# Toilet_Timer.net
KiCad netlist of a schematic drawn in Altium Designer
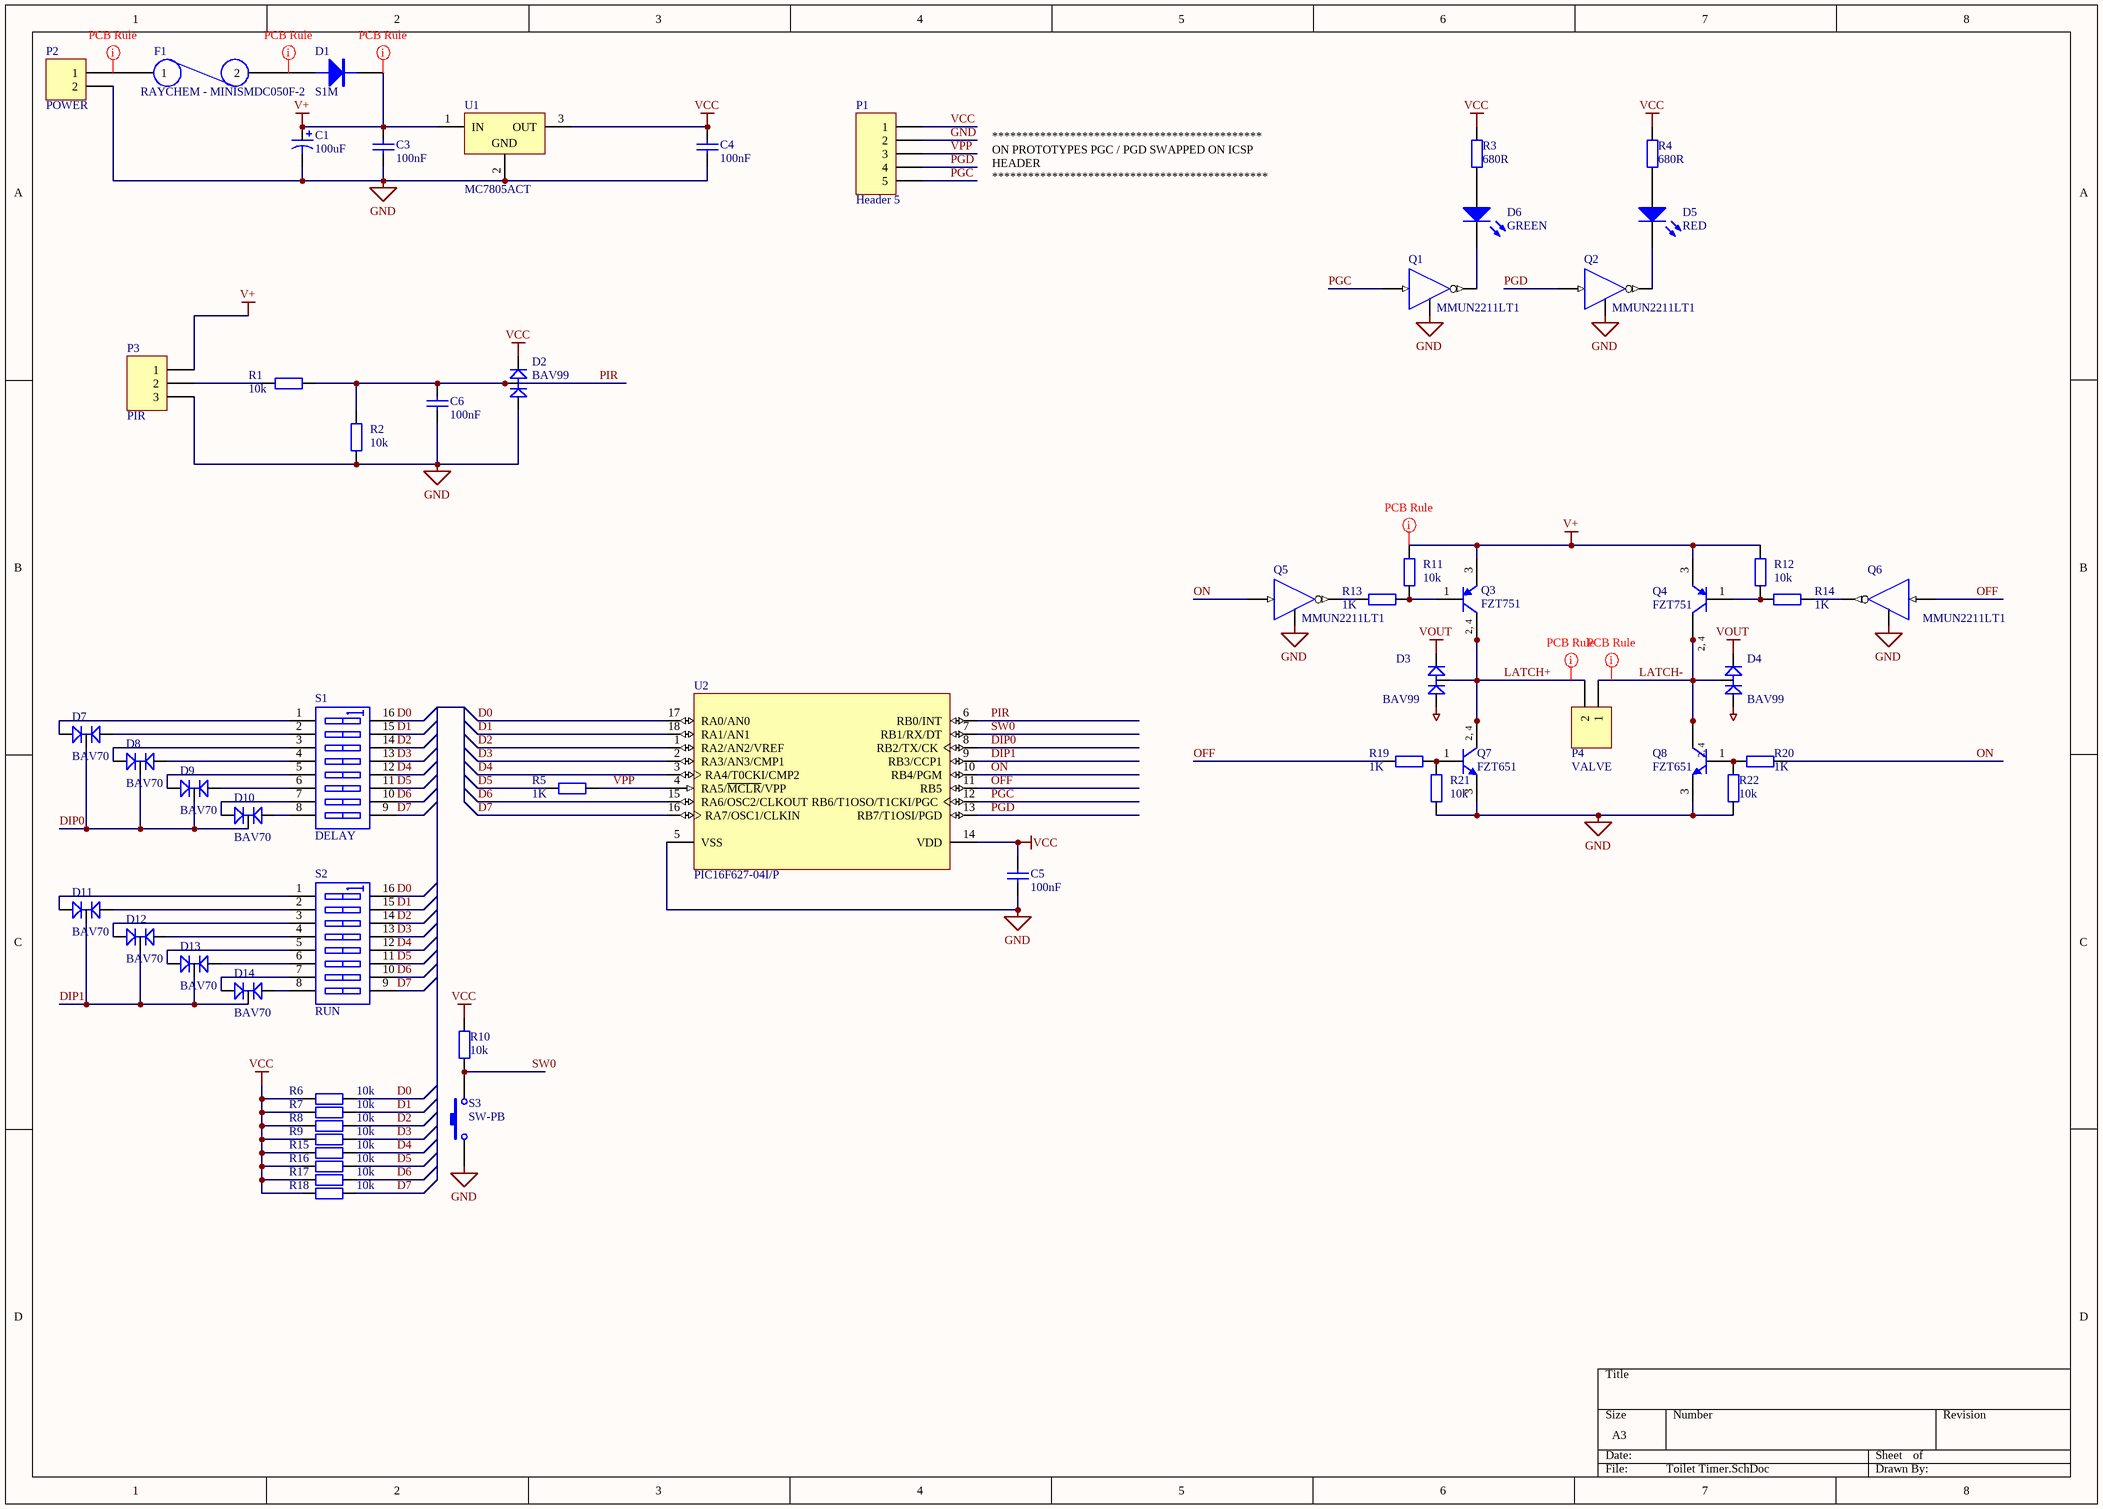
[diagram p0: Toilet Timer.SchDoc]

(export (version "E")
  (design (tool "Eeschema 10.0.6"))
  (components
    (comp (ref "C1")
      (value "100uF")
      (footprint "CAP, SMD E CASE")
      (description "Polarized Capacitor (Radial)")
      (fields (field (name "MOUSER PART NO.") "647-UVR1H101MPD1TA") (field (name "Comment") "Cap Pol1"))
      (libsource (lib "Miscellaneous Devices") (part "Cap Pol1"))
    )
    (comp (ref "C3")
      (value "100nF")
      (footprint "CAP(3D) - 0805")
      (description "Capacitor")
      (fields (field (name "MOUSER PART NO.") "K104Z15Y5VE5TH5") (field (name "Comment") "Cap"))
      (libsource (lib "Miscellaneous Devices") (part "Cap"))
    )
    (comp (ref "C4")
      (value "100nF")
      (footprint "CAP(3D) - 0805")
      (description "Capacitor")
      (fields (field (name "MOUSER PART NO.") "K104Z15Y5VE5TH5") (field (name "Comment") "Cap"))
      (libsource (lib "Miscellaneous Devices") (part "Cap"))
    )
    (comp (ref "C5")
      (value "100nF")
      (footprint "CAP(3D) - 0805")
      (description "Capacitor")
      (fields (field (name "MOUSER PART NO.") "K104Z15Y5VE5TH5") (field (name "Comment") "Cap"))
      (libsource (lib "Miscellaneous Devices") (part "Cap"))
    )
    (comp (ref "C6")
      (value "100nF")
      (footprint "CAP(3D) - 0805")
      (description "Capacitor")
      (fields (field (name "MOUSER PART NO.") "K104Z15Y5VE5TH5") (field (name "Comment") "Cap"))
      (libsource (lib "Miscellaneous Devices") (part "Cap"))
    )
    (comp (ref "D1")
      (value "S1M")
      (footprint "DO-214AC")
      (description "DIODE, POWER")
      (fields (field (name "MOUSER PART NO.") "821-S1M") (field (name "FARNELL PART NO.") "9843841"))
      (libsource (lib "401 CCPA") (part "DIODE"))
    )
    (comp (ref "D2")
      (value "BAV99")
      (footprint "SOT23-3L")
      (description "DUAL DIODE, BAV99")
      (fields (field (name "MOUSER PART NO.") "771-BAV99/T3") (field (name "FARNELL PART NO.") "9843612"))
      (libsource (lib "401 CCPA") (part "BAV99"))
    )
    (comp (ref "D3")
      (value "BAV99")
      (footprint "SOT23-3L")
      (description "DUAL DIODE, BAV99")
      (fields (field (name "MOUSER PART NO.") "771-BAV99/T3") (field (name "FARNELL PART NO.") "9843612"))
      (libsource (lib "401 CCPA") (part "BAV99"))
    )
    (comp (ref "D4")
      (value "BAV99")
      (footprint "SOT23-3L")
      (description "DUAL DIODE, BAV99")
      (fields (field (name "MOUSER PART NO.") "771-BAV99/T3") (field (name "FARNELL PART NO.") "9843612"))
      (libsource (lib "401 CCPA") (part "BAV99"))
    )
    (comp (ref "D5")
      (value "RED")
      (footprint "LED(3D) RED - 0805")
      (description "Typical INFRARED GaAs LED")
      (fields (field (name "MOUSER PART NO.") "606-4308H1"))
      (libsource (lib "Miscellaneous Devices") (part "LED0"))
    )
    (comp (ref "D6")
      (value "GREEN")
      (footprint "LED(3D) GREEN - 0805")
      (description "Typical INFRARED GaAs LED")
      (fields (field (name "MOUSER PART NO.") "606-4308H5"))
      (libsource (lib "Miscellaneous Devices") (part "LED0"))
    )
    (comp (ref "D7")
      (value "BAV70")
      (footprint "SOT23-3L")
      (description "DUAL DIODE, BAV99")
      (fields
        (field (name "FARNELL PART NO.") "9843612")
        (field (name "MANUFACTURER") "FAIRCHILD SEMICONDUCTOR")
      )
      (libsource (lib "Toilet Timer") (part "BAV70"))
    )
    (comp (ref "D8")
      (value "BAV70")
      (footprint "SOT23-3L")
      (description "DUAL DIODE, BAV99")
      (fields
        (field (name "FARNELL PART NO.") "9843612")
        (field (name "MANUFACTURER") "FAIRCHILD SEMICONDUCTOR")
      )
      (libsource (lib "Toilet Timer") (part "BAV70"))
    )
    (comp (ref "D9")
      (value "BAV70")
      (footprint "SOT23-3L")
      (description "DUAL DIODE, BAV99")
      (fields
        (field (name "FARNELL PART NO.") "9843612")
        (field (name "MANUFACTURER") "FAIRCHILD SEMICONDUCTOR")
      )
      (libsource (lib "Toilet Timer") (part "BAV70"))
    )
    (comp (ref "D10")
      (value "BAV70")
      (footprint "SOT23-3L")
      (description "DUAL DIODE, BAV99")
      (fields
        (field (name "FARNELL PART NO.") "9843612")
        (field (name "MANUFACTURER") "FAIRCHILD SEMICONDUCTOR")
      )
      (libsource (lib "Toilet Timer") (part "BAV70"))
    )
    (comp (ref "D11")
      (value "BAV70")
      (footprint "SOT23-3L")
      (description "DUAL DIODE, BAV99")
      (fields
        (field (name "FARNELL PART NO.") "9843612")
        (field (name "MANUFACTURER") "FAIRCHILD SEMICONDUCTOR")
      )
      (libsource (lib "Toilet Timer") (part "BAV70"))
    )
    (comp (ref "D12")
      (value "BAV70")
      (footprint "SOT23-3L")
      (description "DUAL DIODE, BAV99")
      (fields
        (field (name "FARNELL PART NO.") "9843612")
        (field (name "MANUFACTURER") "FAIRCHILD SEMICONDUCTOR")
      )
      (libsource (lib "Toilet Timer") (part "BAV70"))
    )
    (comp (ref "D13")
      (value "BAV70")
      (footprint "SOT23-3L")
      (description "DUAL DIODE, BAV99")
      (fields
        (field (name "FARNELL PART NO.") "9843612")
        (field (name "MANUFACTURER") "FAIRCHILD SEMICONDUCTOR")
      )
      (libsource (lib "Toilet Timer") (part "BAV70"))
    )
    (comp (ref "D14")
      (value "BAV70")
      (footprint "SOT23-3L")
      (description "DUAL DIODE, BAV99")
      (fields
        (field (name "FARNELL PART NO.") "9843612")
        (field (name "MANUFACTURER") "FAIRCHILD SEMICONDUCTOR")
      )
      (libsource (lib "Toilet Timer") (part "BAV70"))
    )
    (comp (ref "F1")
      (value "RAYCHEM - MINISMDC050F-2")
      (footprint "miniSMD Polyswitch")
      (fields
        (field (name "MOUSER PART NO.") "650-MINISMDC050F-2")
        (field (name "FARNELL PART NO.") "1175839")
        (field (name "MANUFACTURER") "Tyco Electronics / Raychem")
      )
      (libsource (lib "401 CCPA") (part "POLYSWITCH"))
    )
    (comp (ref "P1")
      (value "Header 5")
      (footprint "TERMINAL-6 POL")
      (description "Header, 5-Pin")
      (fields (field (name "MOUSER PART NO.") "571-6404565"))
      (libsource (lib "Miscellaneous Connectors") (part "Header 5"))
    )
    (comp (ref "P2")
      (value "POWER")
      (footprint "TYCO  1776112-2")
      (description "Header, 2-Pin")
      (fields (field (name "PUBLISHER") "Altium Limited"))
      (libsource (lib "Miscellaneous Connectors") (part "Header 2"))
    )
    (comp (ref "P3")
      (value "PIR")
      (footprint "TYCO  1776112-3")
      (description "Header, 3-Pin")
      (fields (field (name "PUBLISHER") "Altium Limited"))
      (libsource (lib "Miscellaneous Connectors") (part "Header 3"))
    )
    (comp (ref "P4")
      (value "VALVE")
      (footprint "TYCO  1776112-2")
      (description "Header, 2-Pin")
      (fields (field (name "PUBLISHER") "Altium Limited"))
      (libsource (lib "Miscellaneous Connectors") (part "Header 2"))
    )
    (comp (ref "Q1")
      (value "MMUN2211LT1")
      (footprint "SOT23-3L")
      (fields
        (field (name "MOUSER PART NO.") "863-MMUN2211LT1G")
        (field (name "FARNELL PART NO.") "9556648RL")
        (field (name "MANUFACTURER") "ON Semiconductor")
      )
      (libsource (lib "401 CCPA") (part "NPN DIGITAL TRANSISTOR"))
    )
    (comp (ref "Q2")
      (value "MMUN2211LT1")
      (footprint "SOT23-3L")
      (fields
        (field (name "MOUSER PART NO.") "863-MMUN2211LT1G")
        (field (name "FARNELL PART NO.") "9556648RL")
        (field (name "MANUFACTURER") "ON Semiconductor")
      )
      (libsource (lib "401 CCPA") (part "NPN DIGITAL TRANSISTOR"))
    )
    (comp (ref "Q3")
      (value "FZT751")
      (footprint "SOT223")
      (description "SOT223 PNP Silicon Planar High-Performance Transistor")
      (fields (field (name "PUBLISHER") "Altium Limited"))
      (libsource (lib "Zetex Discrete BJT") (part "FZT751"))
    )
    (comp (ref "Q4")
      (value "FZT751")
      (footprint "SOT223")
      (description "SOT223 PNP Silicon Planar High-Performance Transistor")
      (fields (field (name "PUBLISHER") "Altium Limited"))
      (libsource (lib "Zetex Discrete BJT") (part "FZT751"))
    )
    (comp (ref "Q5")
      (value "MMUN2211LT1")
      (footprint "SOT23-3L")
      (fields
        (field (name "MOUSER PART NO.") "863-MMUN2211LT1G")
        (field (name "FARNELL PART NO.") "9556648RL")
        (field (name "MANUFACTURER") "ON Semiconductor")
      )
      (libsource (lib "401 CCPA") (part "NPN DIGITAL TRANSISTOR"))
    )
    (comp (ref "Q6")
      (value "MMUN2211LT1")
      (footprint "SOT23-3L")
      (fields
        (field (name "MOUSER PART NO.") "863-MMUN2211LT1G")
        (field (name "FARNELL PART NO.") "9556648RL")
        (field (name "MANUFACTURER") "ON Semiconductor")
      )
      (libsource (lib "401 CCPA") (part "NPN DIGITAL TRANSISTOR"))
    )
    (comp (ref "Q7")
      (value "FZT651")
      (footprint "SOT223")
      (description "SOT223 NPN Silicon Planar High-Performance Transistor")
      (fields (field (name "PUBLISHER") "Altium Limited"))
      (libsource (lib "Zetex Discrete BJT") (part "FZT651"))
    )
    (comp (ref "Q8")
      (value "FZT651")
      (footprint "SOT223")
      (description "SOT223 NPN Silicon Planar High-Performance Transistor")
      (fields (field (name "PUBLISHER") "Altium Limited"))
      (libsource (lib "Zetex Discrete BJT") (part "FZT651"))
    )
    (comp (ref "R1")
      (value "10k")
      (footprint "RES(3D) - 0805")
      (description "Resistor")
      (fields (field (name "MOUSER PART NO.") "660-MF1/4LCT52R103J") (field (name "Comment") "Res2"))
      (libsource (lib "") (part "Res2_1"))
    )
    (comp (ref "R2")
      (value "10k")
      (footprint "RES(3D) - 0805")
      (description "Resistor")
      (fields (field (name "MOUSER PART NO.") "660-MF1/4LCT52R103J") (field (name "Comment") "Res2"))
      (libsource (lib "") (part "Res2_2"))
    )
    (comp (ref "R3")
      (value "680R")
      (footprint "RES(3D) - 0805")
      (description "Resistor")
      (fields (field (name "MOUSER PART NO.") "660-MF1/4DCT52R6800F") (field (name "Comment") "Res2"))
      (libsource (lib "") (part "Res2_2"))
    )
    (comp (ref "R4")
      (value "680R")
      (footprint "RES(3D) - 0805")
      (description "Resistor")
      (fields (field (name "MOUSER PART NO.") "660-MF1/4DCT52R6800F") (field (name "Comment") "Res2"))
      (libsource (lib "") (part "Res2_2"))
    )
    (comp (ref "R5")
      (value "1K")
      (footprint "RES(3D) - 0805")
      (description "Resistor")
      (fields (field (name "MOUSER PART NO.") "660-MF1/4DCT52R1102F") (field (name "Comment") "Res2"))
      (libsource (lib "") (part "Res2_1"))
    )
    (comp (ref "R6")
      (value "10k")
      (footprint "RES(3D) - 0805")
      (description "Resistor")
      (fields (field (name "MOUSER PART NO.") "660-MF1/4LCT52R103J") (field (name "Comment") "Res2"))
      (libsource (lib "Miscellaneous Devices") (part "Res2"))
    )
    (comp (ref "R7")
      (value "10k")
      (footprint "RES(3D) - 0805")
      (description "Resistor")
      (fields (field (name "MOUSER PART NO.") "660-MF1/4LCT52R103J") (field (name "Comment") "Res2"))
      (libsource (lib "Miscellaneous Devices") (part "Res2"))
    )
    (comp (ref "R8")
      (value "10k")
      (footprint "RES(3D) - 0805")
      (description "Resistor")
      (fields (field (name "MOUSER PART NO.") "660-MF1/4LCT52R103J") (field (name "Comment") "Res2"))
      (libsource (lib "Miscellaneous Devices") (part "Res2"))
    )
    (comp (ref "R9")
      (value "10k")
      (footprint "RES(3D) - 0805")
      (description "Resistor")
      (fields (field (name "MOUSER PART NO.") "660-MF1/4LCT52R103J") (field (name "Comment") "Res2"))
      (libsource (lib "Miscellaneous Devices") (part "Res2"))
    )
    (comp (ref "R10")
      (value "10k")
      (footprint "RES(3D) - 0805")
      (description "Resistor")
      (fields (field (name "MOUSER PART NO.") "660-MF1/4LCT52R103J") (field (name "Comment") "Res2"))
      (libsource (lib "") (part "Res2_3"))
    )
    (comp (ref "R11")
      (value "10k")
      (footprint "RES(3D) - 0805")
      (description "Resistor")
      (fields (field (name "MOUSER PART NO.") "660-MF1/4LCT52R103J") (field (name "Comment") "Res2"))
      (libsource (lib "") (part "Res2_2"))
    )
    (comp (ref "R12")
      (value "10k")
      (footprint "RES(3D) - 0805")
      (description "Resistor")
      (fields (field (name "MOUSER PART NO.") "660-MF1/4LCT52R103J") (field (name "Comment") "Res2"))
      (libsource (lib "") (part "Res2_2"))
    )
    (comp (ref "R13")
      (value "1K")
      (footprint "RES(3D) - 0805")
      (description "Resistor")
      (fields (field (name "MOUSER PART NO.") "660-MF1/4DCT52R1102F") (field (name "Comment") "Res2"))
      (libsource (lib "") (part "Res2_1"))
    )
    (comp (ref "R14")
      (value "1K")
      (footprint "RES(3D) - 0805")
      (description "Resistor")
      (fields (field (name "MOUSER PART NO.") "660-MF1/4DCT52R1102F") (field (name "Comment") "Res2"))
      (libsource (lib "") (part "Res2_3"))
    )
    (comp (ref "R15")
      (value "10k")
      (footprint "RES(3D) - 0805")
      (description "Resistor")
      (fields (field (name "MOUSER PART NO.") "660-MF1/4LCT52R103J") (field (name "Comment") "Res2"))
      (libsource (lib "Miscellaneous Devices") (part "Res2"))
    )
    (comp (ref "R16")
      (value "10k")
      (footprint "RES(3D) - 0805")
      (description "Resistor")
      (fields (field (name "MOUSER PART NO.") "660-MF1/4LCT52R103J") (field (name "Comment") "Res2"))
      (libsource (lib "Miscellaneous Devices") (part "Res2"))
    )
    (comp (ref "R17")
      (value "10k")
      (footprint "RES(3D) - 0805")
      (description "Resistor")
      (fields (field (name "MOUSER PART NO.") "660-MF1/4LCT52R103J") (field (name "Comment") "Res2"))
      (libsource (lib "Miscellaneous Devices") (part "Res2"))
    )
    (comp (ref "R18")
      (value "10k")
      (footprint "RES(3D) - 0805")
      (description "Resistor")
      (fields (field (name "MOUSER PART NO.") "660-MF1/4LCT52R103J") (field (name "Comment") "Res2"))
      (libsource (lib "Miscellaneous Devices") (part "Res2"))
    )
    (comp (ref "R19")
      (value "1K")
      (footprint "RES(3D) - 0805")
      (description "Resistor")
      (fields (field (name "MOUSER PART NO.") "660-MF1/4DCT52R1102F") (field (name "Comment") "Res2"))
      (libsource (lib "") (part "Res2_1"))
    )
    (comp (ref "R20")
      (value "1K")
      (footprint "RES(3D) - 0805")
      (description "Resistor")
      (fields (field (name "MOUSER PART NO.") "660-MF1/4DCT52R1102F") (field (name "Comment") "Res2"))
      (libsource (lib "") (part "Res2_3"))
    )
    (comp (ref "R21")
      (value "10k")
      (footprint "RES(3D) - 0805")
      (description "Resistor")
      (fields (field (name "MOUSER PART NO.") "660-MF1/4LCT52R103J") (field (name "Comment") "Res2"))
      (libsource (lib "") (part "Res2_2"))
    )
    (comp (ref "R22")
      (value "10k")
      (footprint "RES(3D) - 0805")
      (description "Resistor")
      (fields (field (name "MOUSER PART NO.") "660-MF1/4LCT52R103J") (field (name "Comment") "Res2"))
      (libsource (lib "") (part "Res2_1"))
    )
    (comp (ref "S1")
      (value "DELAY")
      (footprint "S-DIP-16")
      (description "DIP Switch, 8 Position, SPST")
      (fields (field (name "MOUSER PART NO.") "774-2068"))
      (libsource (lib "Miscellaneous Devices") (part "SW DIP-8"))
    )
    (comp (ref "S2")
      (value "RUN")
      (footprint "S-DIP-16")
      (description "DIP Switch, 8 Position, SPST")
      (fields (field (name "MOUSER PART NO.") "774-2068"))
      (libsource (lib "Miscellaneous Devices") (part "SW DIP-8"))
    )
    (comp (ref "S3")
      (value "SW-PB")
      (footprint "TACT 6MM")
      (description "Switch")
      (fields (field (name "MOUSER PART NO.") "642-MJTP1230"))
      (libsource (lib "Miscellaneous Devices") (part "SW-PB"))
    )
    (comp (ref "U1")
      (value "MC7805ACT")
      (footprint "7805 - DPAK")
      (description "3-Terminal Positive Fixed Voltage Regulator")
      (fields (field (name "MOUSER PART NO.") "512-LM7805ACT"))
      (libsource (lib "Motorola Power Mgt Voltage Regulator") (part "MC7805ACT"))
    )
    (comp (ref "U2")
      (value "PIC16F627-04I/P")
      (footprint "SOIC-18")
      (fields (field (name "MOUSER PART NO.") "579-PIC16F627A-I/P"))
      (libsource (lib "Microchip Microcontroller 8-Bit PIC16F") (part "PIC16F627-04I/P"))
    )
  )
  (nets
    (net (code "1") (name "/D0") (class "Default")
      (node (ref "R6") (pin "1") (pinfunction "1_1") (pintype "passive"))
      (node (ref "S1") (pin "16") (pinfunction "B1_16") (pintype "passive"))
      (node (ref "S2") (pin "16") (pinfunction "B1_16") (pintype "passive"))
      (node (ref "U2") (pin "17") (pinfunction "RA0/AN0_17") (pintype "bidirectional"))
    )
    (net (code "2") (name "/D1") (class "Default")
      (node (ref "R7") (pin "1") (pinfunction "1_1") (pintype "passive"))
      (node (ref "S1") (pin "15") (pinfunction "B2_15") (pintype "passive"))
      (node (ref "S2") (pin "15") (pinfunction "B2_15") (pintype "passive"))
      (node (ref "U2") (pin "18") (pinfunction "RA1/AN1_18") (pintype "bidirectional"))
    )
    (net (code "3") (name "/D2") (class "Default")
      (node (ref "R8") (pin "1") (pinfunction "1_1") (pintype "passive"))
      (node (ref "S1") (pin "14") (pinfunction "B3_14") (pintype "passive"))
      (node (ref "S2") (pin "14") (pinfunction "B3_14") (pintype "passive"))
      (node (ref "U2") (pin "1") (pinfunction "RA2/AN2/VREF_1") (pintype "bidirectional"))
    )
    (net (code "4") (name "/D3") (class "Default")
      (node (ref "R9") (pin "1") (pinfunction "1_1") (pintype "passive"))
      (node (ref "S1") (pin "13") (pinfunction "B4_13") (pintype "passive"))
      (node (ref "S2") (pin "13") (pinfunction "B4_13") (pintype "passive"))
      (node (ref "U2") (pin "2") (pinfunction "RA3/AN3/CMP1_2") (pintype "bidirectional"))
    )
    (net (code "5") (name "/D4") (class "Default")
      (node (ref "R15") (pin "1") (pinfunction "1_1") (pintype "passive"))
      (node (ref "S1") (pin "12") (pinfunction "B5_12") (pintype "passive"))
      (node (ref "S2") (pin "12") (pinfunction "B5_12") (pintype "passive"))
      (node (ref "U2") (pin "3") (pinfunction "RA4/T0CKI/CMP2_3") (pintype "bidirectional"))
    )
    (net (code "6") (name "/D5") (class "Default")
      (node (ref "R16") (pin "1") (pinfunction "1_1") (pintype "passive"))
      (node (ref "R5") (pin "1") (pinfunction "1_1") (pintype "passive"))
      (node (ref "S1") (pin "11") (pinfunction "B6_11") (pintype "passive"))
      (node (ref "S2") (pin "11") (pinfunction "B6_11") (pintype "passive"))
    )
    (net (code "7") (name "/D6") (class "Default")
      (node (ref "R17") (pin "1") (pinfunction "1_1") (pintype "passive"))
      (node (ref "S1") (pin "10") (pinfunction "B7_10") (pintype "passive"))
      (node (ref "S2") (pin "10") (pinfunction "B7_10") (pintype "passive"))
      (node (ref "U2") (pin "15") (pinfunction "RA6/OSC2/CLKOUT_15") (pintype "bidirectional"))
    )
    (net (code "8") (name "/D7") (class "Default")
      (node (ref "R18") (pin "1") (pinfunction "1_1") (pintype "passive"))
      (node (ref "S1") (pin "9") (pinfunction "B8_9") (pintype "passive"))
      (node (ref "S2") (pin "9") (pinfunction "B8_9") (pintype "passive"))
      (node (ref "U2") (pin "16") (pinfunction "RA7/OSC1/CLKIN_16") (pintype "bidirectional"))
    )
    (net (code "9") (name "/DIP0") (class "Default")
      (node (ref "D10") (pin "3") (pinfunction "C_3") (pintype "passive"))
      (node (ref "D7") (pin "3") (pinfunction "C_3") (pintype "passive"))
      (node (ref "D8") (pin "3") (pinfunction "C_3") (pintype "passive"))
      (node (ref "D9") (pin "3") (pinfunction "C_3") (pintype "passive"))
      (node (ref "U2") (pin "8") (pinfunction "RB2/TX/CK_8") (pintype "bidirectional"))
    )
    (net (code "10") (name "/DIP1") (class "Default")
      (node (ref "D11") (pin "3") (pinfunction "C_3") (pintype "passive"))
      (node (ref "D12") (pin "3") (pinfunction "C_3") (pintype "passive"))
      (node (ref "D13") (pin "3") (pinfunction "C_3") (pintype "passive"))
      (node (ref "D14") (pin "3") (pinfunction "C_3") (pintype "passive"))
      (node (ref "U2") (pin "9") (pinfunction "RB3/CCP1_9") (pintype "bidirectional"))
    )
    (net (code "11") (name "/LATCH+") (class "Default")
      (node (ref "D3") (pin "3") (pinfunction "C1/A2_3") (pintype "passive"))
      (node (ref "P4") (pin "2") (pinfunction "2_2") (pintype "passive"))
      (node (ref "Q3") (pin "2") (pinfunction "C_2") (pintype "passive"))
      (node (ref "Q3") (pin "4") (pinfunction "C_4") (pintype "passive"))
      (node (ref "Q7") (pin "2") (pinfunction "C_2") (pintype "passive"))
      (node (ref "Q7") (pin "4") (pinfunction "C_4") (pintype "passive"))
    )
    (net (code "12") (name "/LATCH-") (class "Default")
      (node (ref "D4") (pin "3") (pinfunction "C1/A2_3") (pintype "passive"))
      (node (ref "P4") (pin "1") (pinfunction "1_1") (pintype "passive"))
      (node (ref "Q4") (pin "2") (pinfunction "C_2") (pintype "passive"))
      (node (ref "Q4") (pin "4") (pinfunction "C_4") (pintype "passive"))
      (node (ref "Q8") (pin "2") (pinfunction "C_2") (pintype "passive"))
      (node (ref "Q8") (pin "4") (pinfunction "C_4") (pintype "passive"))
    )
    (net (code "13") (name "/OFF") (class "Default")
      (node (ref "Q6") (pin "1") (pinfunction "B_1") (pintype "input"))
      (node (ref "R19") (pin "1") (pinfunction "1_1") (pintype "passive"))
      (node (ref "U2") (pin "11") (pinfunction "RB5_11") (pintype "bidirectional"))
    )
    (net (code "14") (name "/ON") (class "Default")
      (node (ref "Q5") (pin "1") (pinfunction "B_1") (pintype "input"))
      (node (ref "R20") (pin "1") (pinfunction "1_1") (pintype "passive"))
      (node (ref "U2") (pin "10") (pinfunction "RB4/PGM_10") (pintype "bidirectional"))
    )
    (net (code "15") (name "/PGC") (class "Default")
      (node (ref "P1") (pin "5") (pinfunction "5_5") (pintype "passive"))
      (node (ref "Q1") (pin "1") (pinfunction "B_1") (pintype "input"))
      (node (ref "U2") (pin "12") (pinfunction "RB6/T1OSO/T1CKI/PGC_12") (pintype "bidirectional"))
    )
    (net (code "16") (name "/PGD") (class "Default")
      (node (ref "P1") (pin "4") (pinfunction "4_4") (pintype "passive"))
      (node (ref "Q2") (pin "1") (pinfunction "B_1") (pintype "input"))
      (node (ref "U2") (pin "13") (pinfunction "RB7/T1OSI/PGD_13") (pintype "bidirectional"))
    )
    (net (code "17") (name "/PIR") (class "Default")
      (node (ref "C6") (pin "2") (pinfunction "2_2") (pintype "passive"))
      (node (ref "D2") (pin "3") (pinfunction "C1/A2_3") (pintype "passive"))
      (node (ref "R1") (pin "2") (pinfunction "2_2") (pintype "passive"))
      (node (ref "R2") (pin "2") (pinfunction "2_2") (pintype "passive"))
      (node (ref "U2") (pin "6") (pinfunction "RB0/INT_6") (pintype "bidirectional"))
    )
    (net (code "18") (name "/SW0") (class "Default")
      (node (ref "R10") (pin "2") (pinfunction "2_2") (pintype "passive"))
      (node (ref "S3") (pin "2") (pinfunction "2_2") (pintype "passive"))
      (node (ref "U2") (pin "7") (pinfunction "RB1/RX/DT_7") (pintype "bidirectional"))
    )
    (net (code "19") (name "/VPP") (class "Default")
      (node (ref "P1") (pin "3") (pinfunction "3_3") (pintype "passive"))
      (node (ref "R5") (pin "2") (pinfunction "2_2") (pintype "passive"))
      (node (ref "U2") (pin "4") (pinfunction "RA5/~{MCLR}/VPP_4") (pintype "input"))
    )
    (net (code "20") (name "GND") (class "Default")
      (node (ref "C1") (pin "2") (pinfunction "2_2") (pintype "passive"))
      (node (ref "C3") (pin "1") (pinfunction "1_1") (pintype "passive"))
      (node (ref "C4") (pin "1") (pinfunction "1_1") (pintype "passive"))
      (node (ref "C5") (pin "1") (pinfunction "1_1") (pintype "passive"))
      (node (ref "C6") (pin "1") (pinfunction "1_1") (pintype "passive"))
      (node (ref "D2") (pin "1") (pinfunction "A1_1") (pintype "passive"))
      (node (ref "D3") (pin "1") (pinfunction "A1_1") (pintype "passive"))
      (node (ref "D4") (pin "1") (pinfunction "A1_1") (pintype "passive"))
      (node (ref "P1") (pin "2") (pinfunction "2_2") (pintype "passive"))
      (node (ref "P2") (pin "2") (pinfunction "2_2") (pintype "passive"))
      (node (ref "P3") (pin "3") (pinfunction "3_3") (pintype "passive"))
      (node (ref "Q1") (pin "2") (pinfunction "E_2") (pintype "passive"))
      (node (ref "Q2") (pin "2") (pinfunction "E_2") (pintype "passive"))
      (node (ref "Q5") (pin "2") (pinfunction "E_2") (pintype "passive"))
      (node (ref "Q6") (pin "2") (pinfunction "E_2") (pintype "passive"))
      (node (ref "Q7") (pin "3") (pinfunction "E_3") (pintype "passive"))
      (node (ref "Q8") (pin "3") (pinfunction "E_3") (pintype "passive"))
      (node (ref "R2") (pin "1") (pinfunction "1_1") (pintype "passive"))
      (node (ref "R21") (pin "1") (pinfunction "1_1") (pintype "passive"))
      (node (ref "R22") (pin "1") (pinfunction "1_1") (pintype "passive"))
      (node (ref "S3") (pin "1") (pinfunction "1_1") (pintype "passive"))
      (node (ref "U1") (pin "2") (pinfunction "GND_2") (pintype "power_in"))
      (node (ref "U2") (pin "5") (pinfunction "VSS_5") (pintype "power_in"))
    )
    (net (code "21") (name "Net-(D1-A)") (class "Default")
      (node (ref "D1") (pin "1") (pinfunction "A_1") (pintype "passive"))
      (node (ref "F1") (pin "2") (pinfunction "2_2") (pintype "passive"))
    )
    (net (code "22") (name "Net-(D5-A)") (class "Default")
      (node (ref "D5") (pin "1") (pinfunction "A_1") (pintype "passive"))
      (node (ref "R4") (pin "1") (pinfunction "1_1") (pintype "passive"))
    )
    (net (code "23") (name "Net-(D5-K)") (class "Default")
      (node (ref "D5") (pin "2") (pinfunction "K_2") (pintype "passive"))
      (node (ref "Q2") (pin "3") (pinfunction "C_3") (pintype "output"))
    )
    (net (code "24") (name "Net-(D6-A)") (class "Default")
      (node (ref "D6") (pin "1") (pinfunction "A_1") (pintype "passive"))
      (node (ref "R3") (pin "1") (pinfunction "1_1") (pintype "passive"))
    )
    (net (code "25") (name "Net-(D6-K)") (class "Default")
      (node (ref "D6") (pin "2") (pinfunction "K_2") (pintype "passive"))
      (node (ref "Q1") (pin "3") (pinfunction "C_3") (pintype "output"))
    )
    (net (code "26") (name "Net-(D7-A1)") (class "Default")
      (node (ref "D7") (pin "1") (pinfunction "A1_1") (pintype "passive"))
      (node (ref "S1") (pin "2") (pinfunction "A2_2") (pintype "passive"))
    )
    (net (code "27") (name "Net-(D7-A2)") (class "Default")
      (node (ref "D7") (pin "2") (pinfunction "A2_2") (pintype "passive"))
      (node (ref "S1") (pin "1") (pinfunction "A1_1") (pintype "passive"))
    )
    (net (code "28") (name "Net-(D8-A1)") (class "Default")
      (node (ref "D8") (pin "1") (pinfunction "A1_1") (pintype "passive"))
      (node (ref "S1") (pin "4") (pinfunction "A4_4") (pintype "passive"))
    )
    (net (code "29") (name "Net-(D8-A2)") (class "Default")
      (node (ref "D8") (pin "2") (pinfunction "A2_2") (pintype "passive"))
      (node (ref "S1") (pin "3") (pinfunction "A3_3") (pintype "passive"))
    )
    (net (code "30") (name "Net-(D9-A1)") (class "Default")
      (node (ref "D9") (pin "1") (pinfunction "A1_1") (pintype "passive"))
      (node (ref "S1") (pin "6") (pinfunction "A6_6") (pintype "passive"))
    )
    (net (code "31") (name "Net-(D9-A2)") (class "Default")
      (node (ref "D9") (pin "2") (pinfunction "A2_2") (pintype "passive"))
      (node (ref "S1") (pin "5") (pinfunction "A5_5") (pintype "passive"))
    )
    (net (code "32") (name "Net-(D10-A1)") (class "Default")
      (node (ref "D10") (pin "1") (pinfunction "A1_1") (pintype "passive"))
      (node (ref "S1") (pin "8") (pinfunction "A8_8") (pintype "passive"))
    )
    (net (code "33") (name "Net-(D10-A2)") (class "Default")
      (node (ref "D10") (pin "2") (pinfunction "A2_2") (pintype "passive"))
      (node (ref "S1") (pin "7") (pinfunction "A7_7") (pintype "passive"))
    )
    (net (code "34") (name "Net-(D11-A1)") (class "Default")
      (node (ref "D11") (pin "1") (pinfunction "A1_1") (pintype "passive"))
      (node (ref "S2") (pin "2") (pinfunction "A2_2") (pintype "passive"))
    )
    (net (code "35") (name "Net-(D11-A2)") (class "Default")
      (node (ref "D11") (pin "2") (pinfunction "A2_2") (pintype "passive"))
      (node (ref "S2") (pin "1") (pinfunction "A1_1") (pintype "passive"))
    )
    (net (code "36") (name "Net-(D12-A1)") (class "Default")
      (node (ref "D12") (pin "1") (pinfunction "A1_1") (pintype "passive"))
      (node (ref "S2") (pin "4") (pinfunction "A4_4") (pintype "passive"))
    )
    (net (code "37") (name "Net-(D12-A2)") (class "Default")
      (node (ref "D12") (pin "2") (pinfunction "A2_2") (pintype "passive"))
      (node (ref "S2") (pin "3") (pinfunction "A3_3") (pintype "passive"))
    )
    (net (code "38") (name "Net-(D13-A1)") (class "Default")
      (node (ref "D13") (pin "1") (pinfunction "A1_1") (pintype "passive"))
      (node (ref "S2") (pin "6") (pinfunction "A6_6") (pintype "passive"))
    )
    (net (code "39") (name "Net-(D13-A2)") (class "Default")
      (node (ref "D13") (pin "2") (pinfunction "A2_2") (pintype "passive"))
      (node (ref "S2") (pin "5") (pinfunction "A5_5") (pintype "passive"))
    )
    (net (code "40") (name "Net-(D14-A1)") (class "Default")
      (node (ref "D14") (pin "1") (pinfunction "A1_1") (pintype "passive"))
      (node (ref "S2") (pin "8") (pinfunction "A8_8") (pintype "passive"))
    )
    (net (code "41") (name "Net-(D14-A2)") (class "Default")
      (node (ref "D14") (pin "2") (pinfunction "A2_2") (pintype "passive"))
      (node (ref "S2") (pin "7") (pinfunction "A7_7") (pintype "passive"))
    )
    (net (code "42") (name "Net-(F1-Pad1)") (class "Default")
      (node (ref "F1") (pin "1") (pinfunction "1_1") (pintype "passive"))
      (node (ref "P2") (pin "1") (pinfunction "1_1") (pintype "passive"))
    )
    (net (code "43") (name "Net-(P3-Pad2)") (class "Default")
      (node (ref "P3") (pin "2") (pinfunction "2_2") (pintype "passive"))
      (node (ref "R1") (pin "1") (pinfunction "1_1") (pintype "passive"))
    )
    (net (code "44") (name "Net-(Q3-B)") (class "Default")
      (node (ref "Q3") (pin "1") (pinfunction "B_1") (pintype "passive"))
      (node (ref "R11") (pin "1") (pinfunction "1_1") (pintype "passive"))
      (node (ref "R13") (pin "2") (pinfunction "2_2") (pintype "passive"))
    )
    (net (code "45") (name "Net-(Q4-B)") (class "Default")
      (node (ref "Q4") (pin "1") (pinfunction "B_1") (pintype "passive"))
      (node (ref "R12") (pin "1") (pinfunction "1_1") (pintype "passive"))
      (node (ref "R14") (pin "2") (pinfunction "2_2") (pintype "passive"))
    )
    (net (code "46") (name "Net-(Q5-C)") (class "Default")
      (node (ref "Q5") (pin "3") (pinfunction "C_3") (pintype "output"))
      (node (ref "R13") (pin "1") (pinfunction "1_1") (pintype "passive"))
    )
    (net (code "47") (name "Net-(Q6-C)") (class "Default")
      (node (ref "Q6") (pin "3") (pinfunction "C_3") (pintype "output"))
      (node (ref "R14") (pin "1") (pinfunction "1_1") (pintype "passive"))
    )
    (net (code "48") (name "Net-(Q7-B)") (class "Default")
      (node (ref "Q7") (pin "1") (pinfunction "B_1") (pintype "passive"))
      (node (ref "R19") (pin "2") (pinfunction "2_2") (pintype "passive"))
      (node (ref "R21") (pin "2") (pinfunction "2_2") (pintype "passive"))
    )
    (net (code "49") (name "Net-(Q8-B)") (class "Default")
      (node (ref "Q8") (pin "1") (pinfunction "B_1") (pintype "passive"))
      (node (ref "R20") (pin "2") (pinfunction "2_2") (pintype "passive"))
      (node (ref "R22") (pin "2") (pinfunction "2_2") (pintype "passive"))
    )
    (net (code "50") (name "V+") (class "Default")
      (node (ref "C1") (pin "1") (pinfunction "1_1") (pintype "passive"))
      (node (ref "C3") (pin "2") (pinfunction "2_2") (pintype "passive"))
      (node (ref "D1") (pin "2") (pinfunction "K_2") (pintype "passive"))
      (node (ref "P3") (pin "1") (pinfunction "1_1") (pintype "passive"))
      (node (ref "Q3") (pin "3") (pinfunction "E_3") (pintype "passive"))
      (node (ref "Q4") (pin "3") (pinfunction "E_3") (pintype "passive"))
      (node (ref "R11") (pin "2") (pinfunction "2_2") (pintype "passive"))
      (node (ref "R12") (pin "2") (pinfunction "2_2") (pintype "passive"))
      (node (ref "U1") (pin "1") (pinfunction "IN_1") (pintype "power_in"))
    )
    (net (code "51") (name "VCC") (class "Default")
      (node (ref "C4") (pin "2") (pinfunction "2_2") (pintype "passive"))
      (node (ref "C5") (pin "2") (pinfunction "2_2") (pintype "passive"))
      (node (ref "D2") (pin "2") (pinfunction "C2_2") (pintype "passive"))
      (node (ref "P1") (pin "1") (pinfunction "1_1") (pintype "passive"))
      (node (ref "R10") (pin "1") (pinfunction "1_1") (pintype "passive"))
      (node (ref "R15") (pin "2") (pinfunction "2_2") (pintype "passive"))
      (node (ref "R16") (pin "2") (pinfunction "2_2") (pintype "passive"))
      (node (ref "R17") (pin "2") (pinfunction "2_2") (pintype "passive"))
      (node (ref "R18") (pin "2") (pinfunction "2_2") (pintype "passive"))
      (node (ref "R3") (pin "2") (pinfunction "2_2") (pintype "passive"))
      (node (ref "R4") (pin "2") (pinfunction "2_2") (pintype "passive"))
      (node (ref "R6") (pin "2") (pinfunction "2_2") (pintype "passive"))
      (node (ref "R7") (pin "2") (pinfunction "2_2") (pintype "passive"))
      (node (ref "R8") (pin "2") (pinfunction "2_2") (pintype "passive"))
      (node (ref "R9") (pin "2") (pinfunction "2_2") (pintype "passive"))
      (node (ref "U1") (pin "3") (pinfunction "OUT_3") (pintype "power_in"))
      (node (ref "U2") (pin "14") (pinfunction "VDD_14") (pintype "power_in"))
    )
    (net (code "52") (name "VOUT") (class "Default")
      (node (ref "D3") (pin "2") (pinfunction "C2_2") (pintype "passive"))
      (node (ref "D4") (pin "2") (pinfunction "C2_2") (pintype "passive"))
    )
  )
)
